# Sheet1.net
KiCad netlist of a schematic drawn in Altium Designer
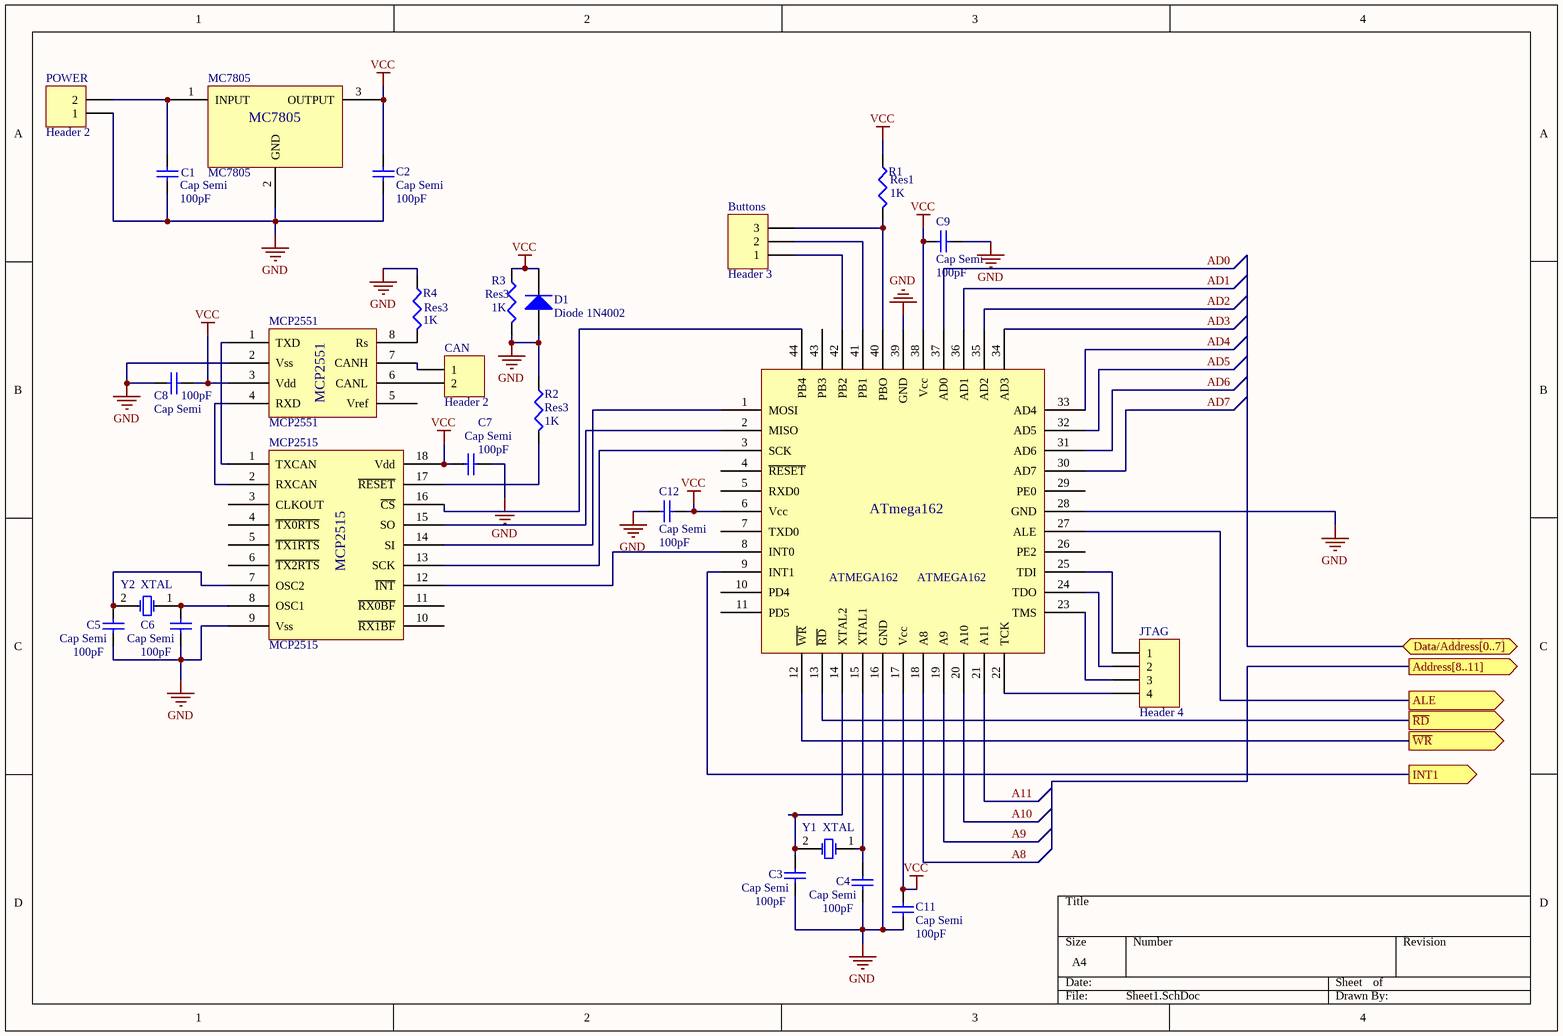
[diagram p0: Sheet1.SchDoc]

(export (version "E")
  (design (tool "Eeschema 10.0.6"))
  (components
    (comp (ref "ATMEGA162")
      (value "ATMEGA162")
      (footprint "ATmega162 TQFP 44-pin")
      (description "Atmega162 MicroControllerUnit")
      (libsource (lib "IIDKLib") (part "ATMEGA162"))
    )
    (comp (ref "Buttons")
      (value "Header 3")
      (footprint "HDR1X3")
      (description "Header, 3-Pin")
      (fields (field (name "PUBLISHER") "Altium Limited"))
      (libsource (lib "Miscellaneous Connectors") (part "Header 3"))
    )
    (comp (ref "C1")
      (value "Cap Semi")
      (footprint "C1210")
      (description "Capacitor (Semiconductor SIM Model)")
      (fields (field (name "ALTIUM_VALUE") "100pF") (field (name "PUBLISHER") "Altium Limited"))
      (libsource (lib "Miscellaneous Devices") (part "Cap Semi"))
    )
    (comp (ref "C2")
      (value "Cap Semi")
      (footprint "C1210")
      (description "Capacitor (Semiconductor SIM Model)")
      (fields (field (name "ALTIUM_VALUE") "100pF") (field (name "PUBLISHER") "Altium Limited"))
      (libsource (lib "Miscellaneous Devices") (part "Cap Semi"))
    )
    (comp (ref "C3")
      (value "Cap Semi")
      (footprint "C1210")
      (description "Capacitor (Semiconductor SIM Model)")
      (fields (field (name "ALTIUM_VALUE") "100pF") (field (name "PUBLISHER") "Altium Limited"))
      (libsource (lib "Miscellaneous Devices") (part "Cap Semi"))
    )
    (comp (ref "C4")
      (value "Cap Semi")
      (footprint "C1210")
      (description "Capacitor (Semiconductor SIM Model)")
      (fields (field (name "ALTIUM_VALUE") "100pF") (field (name "PUBLISHER") "Altium Limited"))
      (libsource (lib "Miscellaneous Devices") (part "Cap Semi"))
    )
    (comp (ref "C5")
      (value "Cap Semi")
      (footprint "C1210")
      (description "Capacitor (Semiconductor SIM Model)")
      (fields (field (name "ALTIUM_VALUE") "100pF") (field (name "PUBLISHER") "Altium Limited"))
      (libsource (lib "Miscellaneous Devices") (part "Cap Semi"))
    )
    (comp (ref "C6")
      (value "Cap Semi")
      (footprint "C1210")
      (description "Capacitor (Semiconductor SIM Model)")
      (fields (field (name "ALTIUM_VALUE") "100pF") (field (name "PUBLISHER") "Altium Limited"))
      (libsource (lib "Miscellaneous Devices") (part "Cap Semi"))
    )
    (comp (ref "C7")
      (value "Cap Semi")
      (footprint "C1210")
      (description "Capacitor (Semiconductor SIM Model)")
      (fields (field (name "ALTIUM_VALUE") "100pF") (field (name "PUBLISHER") "Altium Limited"))
      (libsource (lib "Miscellaneous Devices") (part "Cap Semi"))
    )
    (comp (ref "C8")
      (value "Cap Semi")
      (footprint "C1210")
      (description "Capacitor (Semiconductor SIM Model)")
      (fields (field (name "ALTIUM_VALUE") "100pF") (field (name "PUBLISHER") "Altium Limited"))
      (libsource (lib "Miscellaneous Devices") (part "Cap Semi"))
    )
    (comp (ref "C9")
      (value "Cap Semi")
      (footprint "C1210")
      (description "Capacitor (Semiconductor SIM Model)")
      (fields (field (name "ALTIUM_VALUE") "100pF") (field (name "PUBLISHER") "Altium Limited"))
      (libsource (lib "Miscellaneous Devices") (part "Cap Semi"))
    )
    (comp (ref "C11")
      (value "Cap Semi")
      (footprint "C1210")
      (description "Capacitor (Semiconductor SIM Model)")
      (fields (field (name "ALTIUM_VALUE") "100pF") (field (name "PUBLISHER") "Altium Limited"))
      (libsource (lib "Miscellaneous Devices") (part "Cap Semi"))
    )
    (comp (ref "C12")
      (value "Cap Semi")
      (footprint "C1210")
      (description "Capacitor (Semiconductor SIM Model)")
      (fields (field (name "ALTIUM_VALUE") "100pF") (field (name "PUBLISHER") "Altium Limited"))
      (libsource (lib "Miscellaneous Devices") (part "Cap Semi"))
    )
    (comp (ref "CAN")
      (value "Header 2")
      (footprint "HDR1X2")
      (description "Header, 2-Pin")
      (fields (field (name "PUBLISHER") "Altium Limited"))
      (libsource (lib "Miscellaneous Connectors") (part "Header 2"))
    )
    (comp (ref "D1")
      (value "Diode 1N4002")
      (footprint "DO-41")
      (description "1 Amp General Purpose Rectifier")
      (fields (field (name "PUBLISHER") "Altium Limited"))
      (libsource (lib "Miscellaneous Devices") (part "Diode 1N4002"))
    )
    (comp (ref "JTAG")
      (value "Header 4")
      (footprint "HDR1X4")
      (description "Header, 4-Pin")
      (fields (field (name "PUBLISHER") "Altium Limited"))
      (libsource (lib "Miscellaneous Connectors") (part "Header 4"))
    )
    (comp (ref "MC7805")
      (value "MC7805")
      (footprint "IIDKLib:MC7805 DPAK 3-PIN")
      (description "MC7805 Voltage Regulator")
      (libsource (lib "IIDKLib") (part "MC7805"))
    )
    (comp (ref "MCP2515")
      (value "MCP2515")
      (footprint "MCP2515 SOIC 18-PIN")
      (description "CAN controller")
      (libsource (lib "IIDKLib") (part "MCP2515"))
    )
    (comp (ref "MCP2551")
      (value "MCP2551")
      (footprint "MACP2551 SOIC 8-PIN")
      (description "CAN Transceiver")
      (libsource (lib "IIDKLib") (part "MCP2551"))
    )
    (comp (ref "POWER")
      (value "Header 2")
      (footprint "HDR1X2")
      (description "Header, 2-Pin")
      (fields (field (name "PUBLISHER") "Altium Limited"))
      (libsource (lib "") (part "Header 2_1"))
    )
    (comp (ref "R1")
      (value "Res1")
      (footprint "14-1210")
      (description "Resistor")
      (fields (field (name "ALTIUM_VALUE") "1K") (field (name "PUBLISHER") "Altium Limited"))
      (libsource (lib "Miscellaneous Devices") (part "Res3"))
    )
    (comp (ref "R2")
      (value "Res3")
      (footprint "J1-0603")
      (description "Resistor")
      (fields (field (name "ALTIUM_VALUE") "1K") (field (name "PUBLISHER") "Altium Limited"))
      (libsource (lib "Miscellaneous Devices") (part "Res3"))
    )
    (comp (ref "R3")
      (value "Res3")
      (footprint "J1-0603")
      (description "Resistor")
      (fields (field (name "ALTIUM_VALUE") "1K") (field (name "PUBLISHER") "Altium Limited"))
      (libsource (lib "Miscellaneous Devices") (part "Res3"))
    )
    (comp (ref "R4")
      (value "Res3")
      (footprint "J1-0603")
      (description "Resistor")
      (fields (field (name "ALTIUM_VALUE") "1K") (field (name "PUBLISHER") "Altium Limited"))
      (libsource (lib "Miscellaneous Devices") (part "Res3"))
    )
    (comp (ref "Y1")
      (value "XTAL")
      (footprint "R38")
      (description "Crystal Oscillator")
      (fields (field (name "PUBLISHER") "Altium Limited"))
      (libsource (lib "Miscellaneous Devices") (part "XTAL"))
    )
    (comp (ref "Y2")
      (value "XTAL")
      (footprint "R38")
      (description "Crystal Oscillator")
      (fields (field (name "PUBLISHER") "Altium Limited"))
      (libsource (lib "Miscellaneous Devices") (part "XTAL"))
    )
  )
  (nets
    (net (code "13") (name "/A8") (class "Default")
      (node (ref "ATMEGA162") (pin "18") (pinfunction "A8_18") (pintype "passive"))
    )
    (net (code "14") (name "/A9") (class "Default")
      (node (ref "ATMEGA162") (pin "19") (pinfunction "A9_19") (pintype "passive"))
    )
    (net (code "15") (name "/A10") (class "Default")
      (node (ref "ATMEGA162") (pin "20") (pinfunction "A10_20") (pintype "passive"))
    )
    (net (code "16") (name "/A11") (class "Default")
      (node (ref "ATMEGA162") (pin "21") (pinfunction "A11_21") (pintype "passive"))
    )
    (net (code "17") (name "/AD0") (class "Default")
      (node (ref "ATMEGA162") (pin "37") (pinfunction "AD0_37") (pintype "passive"))
    )
    (net (code "18") (name "/AD1") (class "Default")
      (node (ref "ATMEGA162") (pin "36") (pinfunction "AD1_36") (pintype "passive"))
    )
    (net (code "19") (name "/AD2") (class "Default")
      (node (ref "ATMEGA162") (pin "35") (pinfunction "AD2_35") (pintype "passive"))
    )
    (net (code "20") (name "/AD3") (class "Default")
      (node (ref "ATMEGA162") (pin "34") (pinfunction "AD3_34") (pintype "passive"))
    )
    (net (code "21") (name "/AD4") (class "Default")
      (node (ref "ATMEGA162") (pin "33") (pinfunction "AD4_33") (pintype "passive"))
    )
    (net (code "22") (name "/AD5") (class "Default")
      (node (ref "ATMEGA162") (pin "32") (pinfunction "AD5_32") (pintype "passive"))
    )
    (net (code "23") (name "/AD6") (class "Default")
      (node (ref "ATMEGA162") (pin "31") (pinfunction "AD6_31") (pintype "passive"))
    )
    (net (code "24") (name "/AD7") (class "Default")
      (node (ref "ATMEGA162") (pin "30") (pinfunction "AD7_30") (pintype "passive"))
    )
    (net (code "25") (name "/ALE") (class "Default")
      (node (ref "ATMEGA162") (pin "27") (pinfunction "ALE_27") (pintype "passive"))
    )
    (net (code "28") (name "/INT1") (class "Default")
      (node (ref "ATMEGA162") (pin "9") (pinfunction "INT1_9") (pintype "passive"))
    )
    (net (code "29") (name "/~{RD}") (class "Default")
      (node (ref "ATMEGA162") (pin "13") (pinfunction "~{RD}_13") (pintype "passive"))
    )
    (net (code "30") (name "/~{WR}") (class "Default")
      (node (ref "ATMEGA162") (pin "12") (pinfunction "~{WR}_12") (pintype "passive"))
    )
    (net (code "31") (name "GND") (class "Default")
      (node (ref "ATMEGA162") (pin "16") (pinfunction "GND_16") (pintype "passive"))
      (node (ref "ATMEGA162") (pin "28") (pinfunction "GND_28") (pintype "passive"))
      (node (ref "ATMEGA162") (pin "39") (pinfunction "GND_39") (pintype "passive"))
      (node (ref "C1") (pin "1") (pinfunction "1_1") (pintype "passive"))
      (node (ref "C11") (pin "2") (pinfunction "2_2") (pintype "passive"))
      (node (ref "C12") (pin "2") (pinfunction "2_2") (pintype "passive"))
      (node (ref "C2") (pin "1") (pinfunction "1_1") (pintype "passive"))
      (node (ref "C3") (pin "2") (pinfunction "2_2") (pintype "passive"))
      (node (ref "C4") (pin "1") (pinfunction "1_1") (pintype "passive"))
      (node (ref "C5") (pin "2") (pinfunction "2_2") (pintype "passive"))
      (node (ref "C6") (pin "2") (pinfunction "2_2") (pintype "passive"))
      (node (ref "C7") (pin "1") (pinfunction "1_1") (pintype "passive"))
      (node (ref "C8") (pin "2") (pinfunction "2_2") (pintype "passive"))
      (node (ref "C9") (pin "2") (pinfunction "2_2") (pintype "passive"))
      (node (ref "D1") (pin "1") (pinfunction "A_1") (pintype "passive"))
      (node (ref "MC7805") (pin "2") (pinfunction "GND_2") (pintype "passive"))
      (node (ref "MCP2515") (pin "9") (pinfunction "Vss_9") (pintype "passive"))
      (node (ref "MCP2551") (pin "2") (pinfunction "Vss_2") (pintype "power_in"))
      (node (ref "POWER") (pin "1") (pinfunction "1_1") (pintype "passive"))
      (node (ref "R2") (pin "1") (pinfunction "1_1") (pintype "passive"))
      (node (ref "R3") (pin "2") (pinfunction "2_2") (pintype "passive"))
      (node (ref "R4") (pin "1") (pinfunction "1_1") (pintype "passive"))
    )
    (net (code "32") (name "Net-(ATMEGA162-INT0)") (class "Default")
      (node (ref "ATMEGA162") (pin "8") (pinfunction "INT0_8") (pintype "passive"))
      (node (ref "MCP2515") (pin "12") (pinfunction "~{INT}_12") (pintype "passive"))
    )
    (net (code "33") (name "Net-(ATMEGA162-MISO)") (class "Default")
      (node (ref "ATMEGA162") (pin "2") (pinfunction "MISO_2") (pintype "passive"))
      (node (ref "MCP2515") (pin "15") (pinfunction "SO_15") (pintype "passive"))
    )
    (net (code "34") (name "Net-(ATMEGA162-MOSI)") (class "Default")
      (node (ref "ATMEGA162") (pin "1") (pinfunction "MOSI_1") (pintype "passive"))
      (node (ref "MCP2515") (pin "14") (pinfunction "SI_14") (pintype "passive"))
    )
    (net (code "35") (name "Net-(ATMEGA162-PB1)") (class "Default")
      (node (ref "ATMEGA162") (pin "41") (pinfunction "PB1_41") (pintype "passive"))
      (node (ref "Buttons") (pin "2") (pinfunction "2_2") (pintype "passive"))
    )
    (net (code "36") (name "Net-(ATMEGA162-PB2)") (class "Default")
      (node (ref "ATMEGA162") (pin "42") (pinfunction "PB2_42") (pintype "passive"))
      (node (ref "Buttons") (pin "1") (pinfunction "1_1") (pintype "passive"))
    )
    (net (code "37") (name "Net-(ATMEGA162-PB4)") (class "Default")
      (node (ref "ATMEGA162") (pin "44") (pinfunction "PB4_44") (pintype "passive"))
      (node (ref "MCP2515") (pin "16") (pinfunction "~{CS}_16") (pintype "passive"))
    )
    (net (code "38") (name "Net-(ATMEGA162-PBO)") (class "Default")
      (node (ref "ATMEGA162") (pin "40") (pinfunction "PBO_40") (pintype "passive"))
      (node (ref "Buttons") (pin "3") (pinfunction "3_3") (pintype "passive"))
      (node (ref "R1") (pin "2") (pinfunction "2_2") (pintype "passive"))
    )
    (net (code "39") (name "Net-(ATMEGA162-SCK)") (class "Default")
      (node (ref "ATMEGA162") (pin "3") (pinfunction "SCK_3") (pintype "passive"))
      (node (ref "MCP2515") (pin "13") (pinfunction "SCK_13") (pintype "passive"))
    )
    (net (code "40") (name "Net-(ATMEGA162-TCK)") (class "Default")
      (node (ref "ATMEGA162") (pin "22") (pinfunction "TCK_22") (pintype "passive"))
      (node (ref "JTAG") (pin "4") (pinfunction "4_4") (pintype "passive"))
    )
    (net (code "41") (name "Net-(ATMEGA162-TDI)") (class "Default")
      (node (ref "ATMEGA162") (pin "25") (pinfunction "TDI_25") (pintype "passive"))
      (node (ref "JTAG") (pin "1") (pinfunction "1_1") (pintype "passive"))
    )
    (net (code "42") (name "Net-(ATMEGA162-TDO)") (class "Default")
      (node (ref "ATMEGA162") (pin "24") (pinfunction "TDO_24") (pintype "passive"))
      (node (ref "JTAG") (pin "2") (pinfunction "2_2") (pintype "passive"))
    )
    (net (code "43") (name "Net-(ATMEGA162-TMS)") (class "Default")
      (node (ref "ATMEGA162") (pin "23") (pinfunction "TMS_23") (pintype "passive"))
      (node (ref "JTAG") (pin "3") (pinfunction "3_3") (pintype "passive"))
    )
    (net (code "44") (name "Net-(ATMEGA162-XTAL1)") (class "Default")
      (node (ref "ATMEGA162") (pin "15") (pinfunction "XTAL1_15") (pintype "passive"))
      (node (ref "C4") (pin "2") (pinfunction "2_2") (pintype "passive"))
      (node (ref "Y1") (pin "1") (pinfunction "OSC1_1") (pintype "passive"))
    )
    (net (code "45") (name "Net-(ATMEGA162-XTAL2)") (class "Default")
      (node (ref "ATMEGA162") (pin "14") (pinfunction "XTAL2_14") (pintype "passive"))
      (node (ref "C3") (pin "1") (pinfunction "1_1") (pintype "passive"))
      (node (ref "Y1") (pin "2") (pinfunction "OSC2_2") (pintype "passive"))
    )
    (net (code "46") (name "Net-(MC7805-INPUT)") (class "Default")
      (node (ref "C1") (pin "2") (pinfunction "2_2") (pintype "passive"))
      (node (ref "MC7805") (pin "1") (pinfunction "INPUT_1") (pintype "passive"))
      (node (ref "POWER") (pin "2") (pinfunction "2_2") (pintype "passive"))
    )
    (net (code "47") (name "Net-(MCP2515-OSC1)") (class "Default")
      (node (ref "C6") (pin "1") (pinfunction "1_1") (pintype "passive"))
      (node (ref "MCP2515") (pin "8") (pinfunction "OSC1_8") (pintype "passive"))
      (node (ref "Y2") (pin "1") (pinfunction "OSC1_1") (pintype "passive"))
    )
    (net (code "48") (name "Net-(MCP2515-OSC2)") (class "Default")
      (node (ref "C5") (pin "1") (pinfunction "1_1") (pintype "passive"))
      (node (ref "MCP2515") (pin "7") (pinfunction "OSC2_7") (pintype "passive"))
      (node (ref "Y2") (pin "2") (pinfunction "OSC2_2") (pintype "passive"))
    )
    (net (code "49") (name "Net-(MCP2515-RXCAN)") (class "Default")
      (node (ref "MCP2515") (pin "2") (pinfunction "RXCAN_2") (pintype "passive"))
      (node (ref "MCP2551") (pin "4") (pinfunction "RXD_4") (pintype "passive"))
    )
    (net (code "50") (name "Net-(MCP2515-TXCAN)") (class "Default")
      (node (ref "MCP2515") (pin "1") (pinfunction "TXCAN_1") (pintype "passive"))
      (node (ref "MCP2551") (pin "1") (pinfunction "TXD_1") (pintype "passive"))
    )
    (net (code "51") (name "Net-(MCP2515-~{RESET})") (class "Default")
      (node (ref "MCP2515") (pin "17") (pinfunction "~{RESET}_17") (pintype "passive"))
      (node (ref "R2") (pin "2") (pinfunction "2_2") (pintype "passive"))
    )
    (net (code "52") (name "Net-(MCP2551-CANH)") (class "Default")
      (node (ref "CAN") (pin "1") (pinfunction "1_1") (pintype "passive"))
      (node (ref "MCP2551") (pin "7") (pinfunction "CANH_7") (pintype "passive"))
    )
    (net (code "53") (name "Net-(MCP2551-CANL)") (class "Default")
      (node (ref "CAN") (pin "2") (pinfunction "2_2") (pintype "passive"))
      (node (ref "MCP2551") (pin "6") (pinfunction "CANL_6") (pintype "passive"))
    )
    (net (code "54") (name "Net-(MCP2551-Rs)") (class "Default")
      (node (ref "MCP2551") (pin "8") (pinfunction "Rs_8") (pintype "passive"))
      (node (ref "R4") (pin "2") (pinfunction "2_2") (pintype "passive"))
    )
    (net (code "55") (name "VCC") (class "Default")
      (node (ref "ATMEGA162") (pin "17") (pinfunction "Vcc_17") (pintype "passive"))
      (node (ref "ATMEGA162") (pin "38") (pinfunction "Vcc_38") (pintype "passive"))
      (node (ref "ATMEGA162") (pin "6") (pinfunction "Vcc_6") (pintype "passive"))
      (node (ref "C11") (pin "1") (pinfunction "1_1") (pintype "passive"))
      (node (ref "C12") (pin "1") (pinfunction "1_1") (pintype "passive"))
      (node (ref "C2") (pin "2") (pinfunction "2_2") (pintype "passive"))
      (node (ref "C7") (pin "2") (pinfunction "2_2") (pintype "passive"))
      (node (ref "C8") (pin "1") (pinfunction "1_1") (pintype "passive"))
      (node (ref "C9") (pin "1") (pinfunction "1_1") (pintype "passive"))
      (node (ref "D1") (pin "2") (pinfunction "K_2") (pintype "passive"))
      (node (ref "MC7805") (pin "3") (pinfunction "OUTPUT_3") (pintype "passive"))
      (node (ref "MCP2515") (pin "18") (pinfunction "Vdd_18") (pintype "passive"))
      (node (ref "MCP2551") (pin "3") (pinfunction "Vdd_3") (pintype "power_in"))
      (node (ref "R1") (pin "1") (pinfunction "1_1") (pintype "passive"))
      (node (ref "R3") (pin "1") (pinfunction "1_1") (pintype "passive"))
    )
    (net (code "56") (name "unconnected-(ATMEGA162-PB3-Pad43)") (class "Default")
      (node (ref "ATMEGA162") (pin "43") (pinfunction "PB3_43") (pintype "passive"))
    )
    (net (code "57") (name "unconnected-(ATMEGA162-PD4-Pad10)") (class "Default")
      (node (ref "ATMEGA162") (pin "10") (pinfunction "PD4_10") (pintype "passive"))
    )
    (net (code "58") (name "unconnected-(ATMEGA162-PD5-Pad11)") (class "Default")
      (node (ref "ATMEGA162") (pin "11") (pinfunction "PD5_11") (pintype "passive"))
    )
    (net (code "59") (name "unconnected-(ATMEGA162-PE0-Pad29)") (class "Default")
      (node (ref "ATMEGA162") (pin "29") (pinfunction "PE0_29") (pintype "passive"))
    )
    (net (code "60") (name "unconnected-(ATMEGA162-PE2-Pad26)") (class "Default")
      (node (ref "ATMEGA162") (pin "26") (pinfunction "PE2_26") (pintype "passive"))
    )
    (net (code "61") (name "unconnected-(ATMEGA162-RXD0-Pad5)") (class "Default")
      (node (ref "ATMEGA162") (pin "5") (pinfunction "RXD0_5") (pintype "passive"))
    )
    (net (code "62") (name "unconnected-(ATMEGA162-TXD0-Pad7)") (class "Default")
      (node (ref "ATMEGA162") (pin "7") (pinfunction "TXD0_7") (pintype "passive"))
    )
    (net (code "63") (name "unconnected-(ATMEGA162-~{RESET}-Pad4)") (class "Default")
      (node (ref "ATMEGA162") (pin "4") (pinfunction "~{RESET}_4") (pintype "passive"))
    )
    (net (code "64") (name "unconnected-(MCP2515-CLKOUT-Pad3)") (class "Default")
      (node (ref "MCP2515") (pin "3") (pinfunction "CLKOUT_3") (pintype "passive"))
    )
    (net (code "65") (name "unconnected-(MCP2515-~{RX0BF}-Pad11)") (class "Default")
      (node (ref "MCP2515") (pin "11") (pinfunction "~{RX0BF}_11") (pintype "passive"))
    )
    (net (code "66") (name "unconnected-(MCP2515-~{RX1BF}-Pad10)") (class "Default")
      (node (ref "MCP2515") (pin "10") (pinfunction "~{RX1BF}_10") (pintype "passive"))
    )
    (net (code "67") (name "unconnected-(MCP2515-~{TX0RTS}-Pad4)") (class "Default")
      (node (ref "MCP2515") (pin "4") (pinfunction "~{TX0RTS}_4") (pintype "passive"))
    )
    (net (code "68") (name "unconnected-(MCP2515-~{TX1RTS}-Pad5)") (class "Default")
      (node (ref "MCP2515") (pin "5") (pinfunction "~{TX1RTS}_5") (pintype "passive"))
    )
    (net (code "69") (name "unconnected-(MCP2515-~{TX2RTS}-Pad6)") (class "Default")
      (node (ref "MCP2515") (pin "6") (pinfunction "~{TX2RTS}_6") (pintype "passive"))
    )
    (net (code "70") (name "unconnected-(MCP2551-Vref-Pad5)") (class "Default")
      (node (ref "MCP2551") (pin "5") (pinfunction "Vref_5") (pintype "passive"))
    )
  )
)
